# wacky-hat.net
KiCad netlist of a schematic drawn in Altium Designer
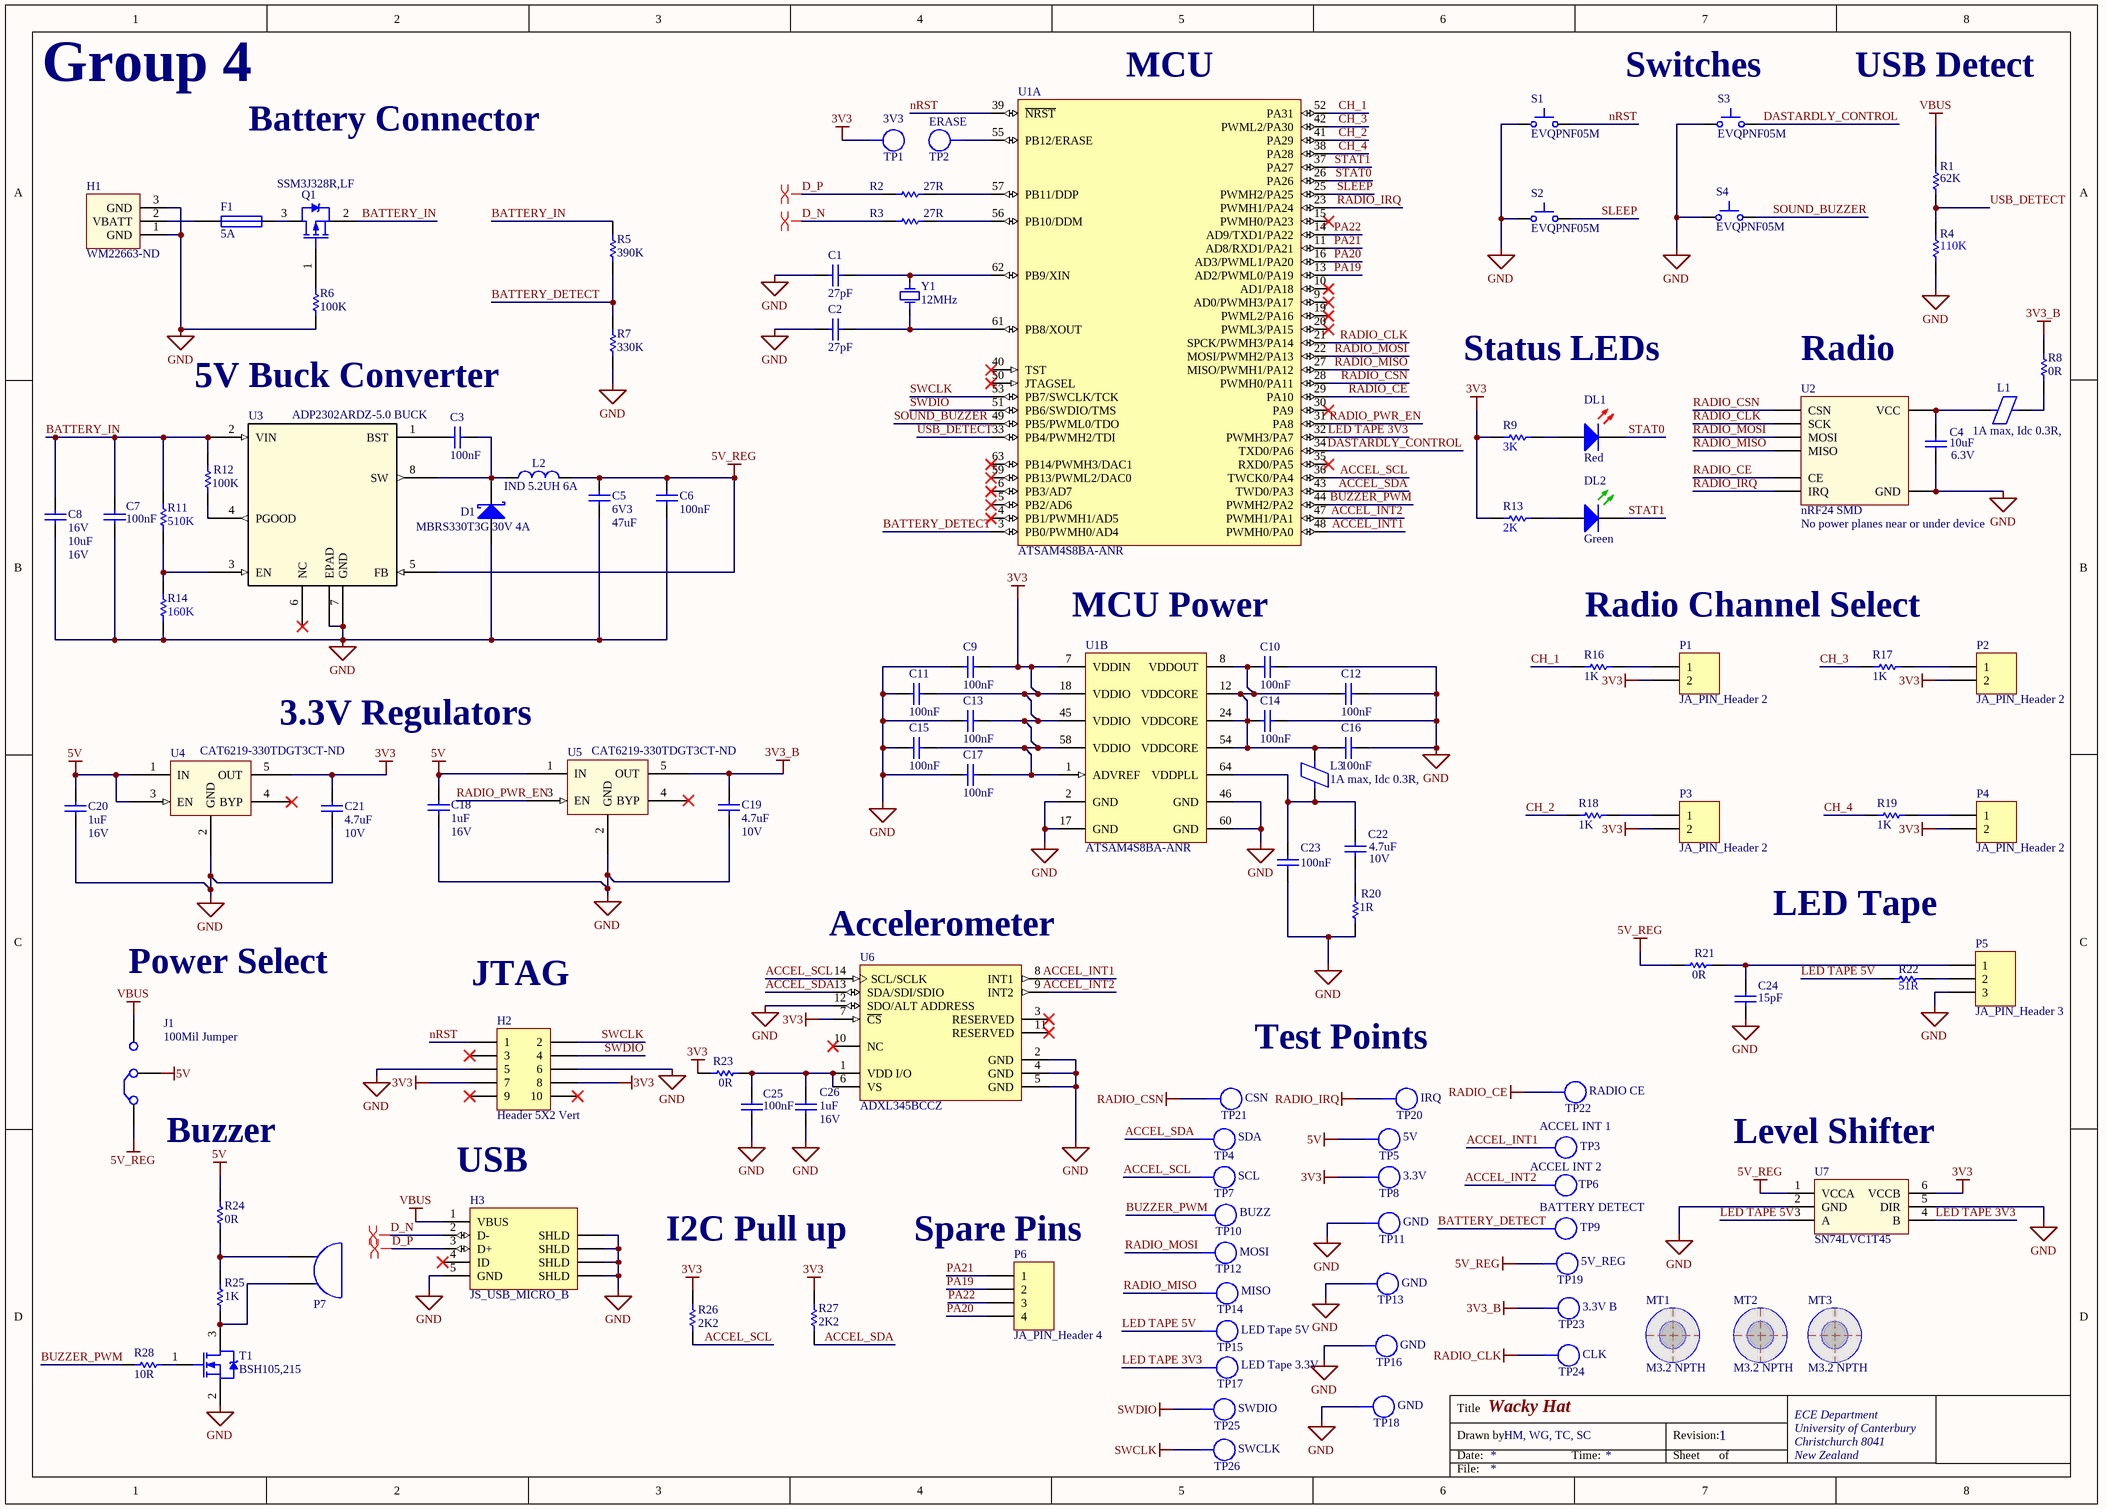
[diagram p0: wacky-hat.SchDoc]

(export (version "E")
  (design (tool "Eeschema 10.0.6"))
  (components
    (comp (ref "C1")
      (value "27pF")
      (footprint "CAPC1608L")
      (description "CAP CER 27pF NPO/COG +-5% 50V 0603")
      (libsource (lib "ECE AD19Components_22V1") (part "CC_27pF_0603"))
    )
    (comp (ref "C2")
      (value "27pF")
      (footprint "CAPC1608L")
      (description "CAP CER 27pF NPO/COG +-5% 50V 0603")
      (libsource (lib "ECE AD19Components_22V1") (part "CC_27pF_0603"))
    )
    (comp (ref "C3")
      (value "100nF")
      (footprint "CAPC1608L")
      (description "CAP CER 100nF X7R +-10% 50V 0603")
      (libsource (lib "ECE AD19Components_22V1") (part "CC_100nF_0603"))
    )
    (comp (ref "C4")
      (value "10uF")
      (footprint "CAPC1608L")
      (description "CAP CER 10UF X5R +-20% 6V3 0603")
      (fields (field (name "VOLTAGE - RATED") "6.3V"))
      (libsource (lib "ECE AD19Components_22V1") (part "CC_10uF_0603"))
    )
    (comp (ref "C5")
      (value "CC_47uF_0805_6V3")
      (footprint "CAPC2012N")
      (description "SAMSUNG ELECTRO-MECHANICS - CL21A476MQCLRNC - CAP, 47UF, 6.3V, MLCC, 0805")
      (fields
        (field (name "TOLERANCE") "20%")
        (field (name "VOLTAGE RATING") "6V3")
        (field (name "CAPACITANCE") "47uF")
      )
      (libsource (lib "ECE AD19Components_22V1") (part "CC_47uF_0805_6V3"))
    )
    (comp (ref "C6")
      (value "100nF")
      (footprint "CAPC1608L")
      (description "CAP CER 100nF X7R +-10% 50V 0603")
      (libsource (lib "ECE AD19Components_22V1") (part "CC_100nF_0603"))
    )
    (comp (ref "C7")
      (value "100nF")
      (footprint "CAPC1608L")
      (description "CAP CER 100nF X7R +-10% 50V 0603")
      (libsource (lib "ECE AD19Components_22V1") (part "CC_100nF_0603"))
    )
    (comp (ref "C8")
      (value "10uF")
      (footprint "CAPC2012L")
      (description "CAP CER 10uF X5R 16V 0805")
      (fields
        (field (name "MANUFACTURER") "Samsung Electro-Mechanics")
        (field (name "MANUFACTURER PART NUMBER") "CL21A106KOQNNWE")
        (field (name "VOLTAGE - RATED") "16V")
        (field (name "MAX VOLTAGE") "16V")
      )
      (libsource (lib "ECE AD19Components_22V1") (part "CC_10uF_0805_16V"))
    )
    (comp (ref "C9")
      (value "100nF")
      (footprint "CAPC1608L")
      (description "CAP CER 100nF X7R +-10% 50V 0603")
      (libsource (lib "ECE AD19Components_22V1") (part "CC_100nF_0603"))
    )
    (comp (ref "C10")
      (value "100nF")
      (footprint "CAPC1608L")
      (description "CAP CER 100nF X7R +-10% 50V 0603")
      (libsource (lib "ECE AD19Components_22V1") (part "CC_100nF_0603"))
    )
    (comp (ref "C11")
      (value "100nF")
      (footprint "CAPC1608L")
      (description "CAP CER 100nF X7R +-10% 50V 0603")
      (libsource (lib "ECE AD19Components_22V1") (part "CC_100nF_0603"))
    )
    (comp (ref "C12")
      (value "100nF")
      (footprint "CAPC1608L")
      (description "CAP CER 100nF X7R +-10% 50V 0603")
      (libsource (lib "ECE AD19Components_22V1") (part "CC_100nF_0603"))
    )
    (comp (ref "C13")
      (value "100nF")
      (footprint "CAPC1608L")
      (description "CAP CER 100nF X7R +-10% 50V 0603")
      (libsource (lib "ECE AD19Components_22V1") (part "CC_100nF_0603"))
    )
    (comp (ref "C14")
      (value "100nF")
      (footprint "CAPC1608L")
      (description "CAP CER 100nF X7R +-10% 50V 0603")
      (libsource (lib "ECE AD19Components_22V1") (part "CC_100nF_0603"))
    )
    (comp (ref "C15")
      (value "100nF")
      (footprint "CAPC1608L")
      (description "CAP CER 100nF X7R +-10% 50V 0603")
      (libsource (lib "ECE AD19Components_22V1") (part "CC_100nF_0603"))
    )
    (comp (ref "C16")
      (value "100nF")
      (footprint "CAPC1608L")
      (description "CAP CER 100nF X7R +-10% 50V 0603")
      (libsource (lib "ECE AD19Components_22V1") (part "CC_100nF_0603"))
    )
    (comp (ref "C17")
      (value "100nF")
      (footprint "CAPC1608L")
      (description "CAP CER 100nF X7R +-10% 50V 0603")
      (libsource (lib "ECE AD19Components_22V1") (part "CC_100nF_0603"))
    )
    (comp (ref "C18")
      (value "1uF")
      (footprint "CAPC1608L")
      (description "CAP CER 1uF Y5V -20% +80% 16V 0603")
      (fields (field (name "MAX VOLTAGE") "16V"))
      (libsource (lib "ECE AD19Components_22V1") (part "CC_1uF_0603"))
    )
    (comp (ref "C19")
      (value "4.7uF")
      (footprint "CAPC1608N")
      (description "CAP CER 4.7uF X5R +-20%  10V 0603")
      (fields (field (name "MAX VOLTAGE") "10V"))
      (libsource (lib "ECE AD19Components_22V1") (part "CC_4.7uF_0603"))
    )
    (comp (ref "C20")
      (value "1uF")
      (footprint "CAPC1608L")
      (description "CAP CER 1uF Y5V -20% +80% 16V 0603")
      (fields (field (name "MAX VOLTAGE") "16V"))
      (libsource (lib "ECE AD19Components_22V1") (part "CC_1uF_0603"))
    )
    (comp (ref "C21")
      (value "4.7uF")
      (footprint "CAPC1608N")
      (description "CAP CER 4.7uF X5R +-20%  10V 0603")
      (fields (field (name "MAX VOLTAGE") "10V"))
      (libsource (lib "ECE AD19Components_22V1") (part "CC_4.7uF_0603"))
    )
    (comp (ref "C22")
      (value "4.7uF")
      (footprint "CAPC1608N")
      (description "CAP CER 4.7uF X5R +-20%  10V 0603")
      (fields (field (name "MAX VOLTAGE") "10V"))
      (libsource (lib "ECE AD19Components_22V1") (part "CC_4.7uF_0603"))
    )
    (comp (ref "C23")
      (value "100nF")
      (footprint "CAPC1608L")
      (description "CAP CER 100nF X7R +-10% 50V 0603")
      (libsource (lib "ECE AD19Components_22V1") (part "CC_100nF_0603"))
    )
    (comp (ref "C24")
      (value "15pF")
      (footprint "CAPC1608L")
      (description "CAP CER 15pF NPO/COG +-5% 50V 0603")
      (libsource (lib "ECE AD19Components_22V1") (part "CC_15pF_0603"))
    )
    (comp (ref "C25")
      (value "100nF")
      (footprint "CAPC1608L")
      (description "CAP CER 100nF X7R +-10% 50V 0603")
      (libsource (lib "ECE AD19Components_22V1") (part "CC_100nF_0603"))
    )
    (comp (ref "C26")
      (value "1uF")
      (footprint "CAPC1608L")
      (description "CAP CER 1uF Y5V -20% +80% 16V 0603")
      (fields (field (name "MAX VOLTAGE") "16V"))
      (libsource (lib "ECE AD19Components_22V1") (part "CC_1uF_0603"))
    )
    (comp (ref "D1")
      (value "MBRS330T3G 30V 4A")
      (footprint "SMC")
      (description "SCHOTTKY  30V 4A")
      (fields
        (field (name "MANUFACTURER") "ON Semiconductor")
        (field (name "MANUFACTURER PART NUMBER") "MBRS330T3G")
      )
      (libsource (lib "ENCE461AD19_V23") (part "MBRS330T3G"))
    )
    (comp (ref "DL1")
      (value "Red")
      (footprint "WL-SMCW0603")
      (description "LED Red 250mcd 0603 SMD")
      (fields
        (field (name "MANUFACTURER") "WURTH ELEKTRONIK")
        (field (name "MANUFACTURER PART NUMBER") "150060RS75000")
        (field (name "LED COLOUR") "Red")
      )
      (libsource (lib "ECE AD19Components_22V1") (part "DL_150060RS75000"))
    )
    (comp (ref "DL2")
      (value "Green")
      (footprint "WL-SMCW0603")
      (description "LED Green 430mcd 0603 SMD")
      (fields
        (field (name "MANUFACTURER") "WURTH ELEKTRONIK")
        (field (name "MANUFACTURER PART NUMBER") "150060GS75000")
        (field (name "LED COLOUR") "Green")
      )
      (libsource (lib "ECE AD19Components_22V1") (part "DL_150060GS75000"))
    )
    (comp (ref "F1")
      (value "5A")
      (footprint "RESC3216N")
      (description "Fuse 5.0A Fast Acting 1206 SMD")
      (fields (field (name "MANUFACTURER PART NUMBER") "C1F5") (field (name "MANUFACTURER") "Bel TRP"))
      (libsource (lib "ECE AD19Components_22V1") (part "FS_Fuse_5.0A"))
    )
    (comp (ref "H1")
      (value "Battery_HEADER_3pin")
      (footprint "BATT_HEADER_3POS")
      (description "3Pin Header 2.54mm spacing\r\nDigikey #WM22663-ND")
      (fields (field (name "SUPPLIER PART NUMBER 1") "WM22663-ND"))
      (libsource (lib "ENCE461AD19_V23") (part "Battery_HEADER_3pin"))
    )
    (comp (ref "H2")
      (value "Header 5X2 Vert")
      (footprint "IDC2.54-V10D")
      (description "IDC Header, 2,54mm, 10-Pin, Vert")
      (libsource (lib "ECE AD19Components_22V1") (part "JA_HDR_IDC_5X2_VERT"))
    )
    (comp (ref "H3")
      (value "JS_USB_MICRO_B")
      (footprint "FCI_USB_10118194-0001LF")
      (description "CONN USB MICRO B RECPT SMT R/A")
      (fields (field (name "MANUFACTURER") "FCI") (field (name "MANUFACTURER PART NUMBER") "10118194-0001LF"))
      (libsource (lib "ECE AD19Components_22V1") (part "JS_USB_MICRO_B_SMT"))
    )
    (comp (ref "J1")
      (value "100Mil Jumper")
      (footprint "JMP2.54-CO")
      (description "2.54mm Jumper change over, Thru Hole")
      (libsource (lib "ECE AD19Components_22V1") (part "TP_JUMPER_CO"))
    )
    (comp (ref "L1")
      (value "1A max, Idc 0.3R,")
      (footprint "INDC3216L")
      (description "Ferrite Bead, Rdc 0.3R, Z100MHZ 600R, Imax 1A, SMD 1206")
      (fields
        (field (name "MANUFACTURER") "FAIR-RITE")
        (field (name "MANUFACTURER PART NUMBER") "2512066017Y1")
      )
      (libsource (lib "ECE AD19Components_22V1") (part "IN_Ferrite-Bead"))
    )
    (comp (ref "L2")
      (value "IND 5.2UH 6A")
      (footprint "INDUCTOR5u2")
      (description "FIXED IND 5.2UH 6A 22 MOHM SMD")
      (fields
        (field (name "MANUFACTURER") "Sumida America Components Inc.")
        (field (name "MANUFACTURER PART NUMBER") "CDRH104RNP-5R2NC")
      )
      (libsource (lib "ENCE461AD19_V23") (part "CDRH104RNP-5R2NC"))
    )
    (comp (ref "L3")
      (value "1A max, Idc 0.3R,")
      (footprint "INDC3216L")
      (description "Ferrite Bead, Rdc 0.3R, Z100MHZ 600R, Imax 1A, SMD 1206")
      (fields
        (field (name "MANUFACTURER") "FAIR-RITE")
        (field (name "MANUFACTURER PART NUMBER") "2512066017Y1")
      )
      (libsource (lib "ECE AD19Components_22V1") (part "IN_Ferrite-Bead"))
    )
    (comp (ref "MT1")
      (value "M3.2 NPTH")
      (footprint "MNT-HOLE_3.2mm_NPTH")
      (description "Fixing M3.2 Mount Hole NPTH")
      (fields (field (name "MANUFACTURER") "Hi-Q"))
      (libsource (lib "ECE AD19Components_22V1") (part "MC_M3.2_HOLE"))
    )
    (comp (ref "MT2")
      (value "M3.2 NPTH")
      (footprint "MNT-HOLE_3.2mm_NPTH")
      (description "Fixing M3.2 Mount Hole NPTH")
      (fields (field (name "MANUFACTURER") "Hi-Q"))
      (libsource (lib "ECE AD19Components_22V1") (part "MC_M3.2_HOLE"))
    )
    (comp (ref "MT3")
      (value "M3.2 NPTH")
      (footprint "MNT-HOLE_3.2mm_NPTH")
      (description "Fixing M3.2 Mount Hole NPTH")
      (fields (field (name "MANUFACTURER") "Hi-Q"))
      (libsource (lib "ECE AD19Components_22V1") (part "MC_M3.2_HOLE"))
    )
    (comp (ref "P1")
      (value "JA_PIN_Header 2")
      (footprint "HDR1X2")
      (description "Header, 2-Pin")
      (fields (field (name "PUBLISHER") "Altium Limited"))
      (libsource (lib "ECE AD19Components_22V1") (part "JA_PIN_Header 2"))
    )
    (comp (ref "P2")
      (value "JA_PIN_Header 2")
      (footprint "HDR1X2")
      (description "Header, 2-Pin")
      (fields (field (name "PUBLISHER") "Altium Limited"))
      (libsource (lib "ECE AD19Components_22V1") (part "JA_PIN_Header 2"))
    )
    (comp (ref "P3")
      (value "JA_PIN_Header 2")
      (footprint "HDR1X2")
      (description "Header, 2-Pin")
      (fields (field (name "PUBLISHER") "Altium Limited"))
      (libsource (lib "ECE AD19Components_22V1") (part "JA_PIN_Header 2"))
    )
    (comp (ref "P4")
      (value "JA_PIN_Header 2")
      (footprint "HDR1X2")
      (description "Header, 2-Pin")
      (fields (field (name "PUBLISHER") "Altium Limited"))
      (libsource (lib "ECE AD19Components_22V1") (part "JA_PIN_Header 2"))
    )
    (comp (ref "P5")
      (value "JA_PIN_Header 3")
      (footprint "HDR1X3")
      (description "Header, 3-Pin")
      (fields (field (name "PUBLISHER") "Altium Limited"))
      (libsource (lib "ECE AD19Components_22V1") (part "JA_PIN_Header 3"))
    )
    (comp (ref "P6")
      (value "JA_PIN_Header 4")
      (footprint "HDR1X4")
      (description "Header, 4-Pin")
      (fields (field (name "PUBLISHER") "Altium Limited"))
      (libsource (lib "ECE AD19Components_22V1") (part "JA_PIN_Header 4"))
    )
    (comp (ref "P7")
      (value "Piezo Buzzer")
      (footprint "BUZZER")
      (description "TDK - PS1240P02BT - BUZZER, PIEZO, 70DB, 12.2MM")
      (libsource (lib "ENCE461AD19_V23") (part "Piezo Buzzer"))
    )
    (comp (ref "Q1")
      (value "SSM3J328R,LF")
      (footprint "SOT23_L")
      (description "MOSFET P-CH 20V 6A SOT23-3")
      (fields
        (field (name "MANUFACTURER") "Toshiba")
        (field (name "MANUFACTURER PART NUMBER") "SSM3J328R,LF")
      )
      (libsource (lib "ECE AD19Components_22V1") (part "TM_SSM3J328R"))
    )
    (comp (ref "R1")
      (value "62K")
      (footprint "RESC1608L")
      (description "RES 62.0K OHM 1/10W 5% 0603 SMD")
      (libsource (lib "ECE AD19Components_22V1") (part "RS_62K"))
    )
    (comp (ref "R2")
      (value "27R")
      (footprint "RESC1608L")
      (description "RES 27 OHM 1/10W 5% 0603 SMD")
      (libsource (lib "ECE AD19Components_22V1") (part "RS_27R"))
    )
    (comp (ref "R3")
      (value "27R")
      (footprint "RESC1608L")
      (description "RES 27 OHM 1/10W 5% 0603 SMD")
      (libsource (lib "ECE AD19Components_22V1") (part "RS_27R"))
    )
    (comp (ref "R4")
      (value "110K")
      (footprint "RESC1608L")
      (description "RES 110K OHM 1/10W 5% 0603 SMD")
      (libsource (lib "ECE AD19Components_22V1") (part "RS_110K"))
    )
    (comp (ref "R5")
      (value "390K")
      (footprint "RESC1608L")
      (description "RES 390K OHM 1/10W 5% 0603 SMD")
      (libsource (lib "ECE AD19Components_22V1") (part "RS_390K"))
    )
    (comp (ref "R6")
      (value "100K")
      (footprint "RESC1608L")
      (description "RES 100K OHM 1/10W 5% 0603 SMD")
      (libsource (lib "ECE AD19Components_22V1") (part "RS_100K"))
    )
    (comp (ref "R7")
      (value "330K")
      (footprint "RESC1608L")
      (description "RES 330K OHM 1/10W 5% 0603 SMD")
      (libsource (lib "ECE AD19Components_22V1") (part "RS_330K"))
    )
    (comp (ref "R8")
      (value "0R")
      (footprint "RESC1608L")
      (description "RES 0.0 OHM 1/10W 5% 0603 SMD")
      (libsource (lib "ECE AD19Components_22V1") (part "RS_0R0"))
    )
    (comp (ref "R9")
      (value "3K")
      (footprint "RESC1608L")
      (description "RES 3K OHM 1/10W 5% 0603 SMD")
      (libsource (lib "ECE AD19Components_22V1") (part "RS_3K"))
    )
    (comp (ref "R11")
      (value "510K")
      (footprint "RESC1608L")
      (description "RES 510K OHM 1/10W 5% 0603 SMD")
      (libsource (lib "ECE AD19Components_22V1") (part "RS_510K"))
    )
    (comp (ref "R12")
      (value "100K")
      (footprint "RESC1608L")
      (description "RES 100K OHM 1/10W 5% 0603 SMD")
      (libsource (lib "ECE AD19Components_22V1") (part "RS_100K"))
    )
    (comp (ref "R13")
      (value "2K")
      (footprint "RESC1608L")
      (description "RES 2K OHM 1/10W 5% 0603 SMD")
      (libsource (lib "ECE AD19Components_22V1") (part "RS_2K"))
    )
    (comp (ref "R14")
      (value "160K")
      (footprint "RESC1608L")
      (description "RES 160K OHM 1/10W 5% 0603 SMD")
      (libsource (lib "ECE AD19Components_22V1") (part "RS_160K"))
    )
    (comp (ref "R16")
      (value "1K")
      (footprint "RESC1608L")
      (description "RES 1.0K OHM 1/10W 5% 0603 SMD")
      (libsource (lib "ECE AD19Components_22V1") (part "RS_1K"))
    )
    (comp (ref "R17")
      (value "1K")
      (footprint "RESC1608L")
      (description "RES 1.0K OHM 1/10W 5% 0603 SMD")
      (libsource (lib "ECE AD19Components_22V1") (part "RS_1K"))
    )
    (comp (ref "R18")
      (value "1K")
      (footprint "RESC1608L")
      (description "RES 1.0K OHM 1/10W 5% 0603 SMD")
      (libsource (lib "ECE AD19Components_22V1") (part "RS_1K"))
    )
    (comp (ref "R19")
      (value "1K")
      (footprint "RESC1608L")
      (description "RES 1.0K OHM 1/10W 5% 0603 SMD")
      (libsource (lib "ECE AD19Components_22V1") (part "RS_1K"))
    )
    (comp (ref "R20")
      (value "1R")
      (footprint "RESC3216L")
      (description "RES 1R OHM 1/4W 5% 1206 SMD")
      (libsource (lib "ECE AD19Components_22V1") (part "RT_1R"))
    )
    (comp (ref "R21")
      (value "0R")
      (footprint "RESC1608L")
      (description "RES 0.0 OHM 1/10W 5% 0603 SMD")
      (libsource (lib "ECE AD19Components_22V1") (part "RS_0R0"))
    )
    (comp (ref "R22")
      (value "51R")
      (footprint "RESC1608L")
      (description "RES 51 OHM 1/10W 5% 0603 SMD")
      (libsource (lib "ECE AD19Components_22V1") (part "RS_51R"))
    )
    (comp (ref "R23")
      (value "0R")
      (footprint "RESC1608L")
      (description "RES 0.0 OHM 1/10W 5% 0603 SMD")
      (libsource (lib "ECE AD19Components_22V1") (part "RS_0R0"))
    )
    (comp (ref "R24")
      (value "0R")
      (footprint "RESC1608L")
      (description "RES 0.0 OHM 1/10W 5% 0603 SMD")
      (libsource (lib "ECE AD19Components_22V1") (part "RS_0R0"))
    )
    (comp (ref "R25")
      (value "1K")
      (footprint "RESC1608L")
      (description "RES 1.0K OHM 1/10W 5% 0603 SMD")
      (libsource (lib "ECE AD19Components_22V1") (part "RS_1K"))
    )
    (comp (ref "R26")
      (value "2K2")
      (footprint "RESC1608L")
      (description "RES 2.2K OHM 1/10W 5% 0603 SMD")
      (libsource (lib "ECE AD19Components_22V1") (part "RS_2K2"))
    )
    (comp (ref "R27")
      (value "2K2")
      (footprint "RESC1608L")
      (description "RES 2.2K OHM 1/10W 5% 0603 SMD")
      (libsource (lib "ECE AD19Components_22V1") (part "RS_2K2"))
    )
    (comp (ref "R28")
      (value "10R")
      (footprint "RESC1608L")
      (description "RES 10 OHM 1/10W 5% 0603 SMD")
      (libsource (lib "ECE AD19Components_22V1") (part "RS_10R"))
    )
    (comp (ref "S1")
      (value "EVQPNF05M")
      (footprint "EVQPNF05M")
      (description "Panasonic 6 x 3.5mm SMD Light Touch Switch Type SMD")
      (fields (field (name "MANUFACTURER") "Panasonic"))
      (libsource (lib "ECE AD19Components_22V1") (part "WS_EVQPNF05M"))
    )
    (comp (ref "S2")
      (value "EVQPNF05M")
      (footprint "EVQPNF05M")
      (description "Panasonic 6 x 3.5mm SMD Light Touch Switch Type SMD")
      (fields (field (name "MANUFACTURER") "Panasonic"))
      (libsource (lib "ECE AD19Components_22V1") (part "WS_EVQPNF05M"))
    )
    (comp (ref "S3")
      (value "EVQPNF05M")
      (footprint "EVQPNF05M")
      (description "Panasonic 6 x 3.5mm SMD Light Touch Switch Type SMD")
      (fields (field (name "MANUFACTURER") "Panasonic"))
      (libsource (lib "ECE AD19Components_22V1") (part "WS_EVQPNF05M"))
    )
    (comp (ref "S4")
      (value "EVQPNF05M")
      (footprint "EVQPNF05M")
      (description "Panasonic 6 x 3.5mm SMD Light Touch Switch Type SMD")
      (fields (field (name "MANUFACTURER") "Panasonic"))
      (libsource (lib "ECE AD19Components_22V1") (part "WS_EVQPNF05M"))
    )
    (comp (ref "T1")
      (value "BSH105,215")
      (footprint "SOT23_L")
      (description "MOSFET N-CH 20V 1.05A SOT-23")
      (fields
        (field (name "MANUFACTURER") "NXP Semiconductors")
        (field (name "MANUFACTURER PART NUMBER") "BSH105,215")
      )
      (libsource (lib "ECE AD19Components_22V1") (part "TM_BSH105"))
    )
    (comp (ref "TP1")
      (value "3V3")
      (footprint "TP_1206")
      (description "Test-Point 3.3x1.6x2.1mm SMD")
      (fields
        (field (name "MANUFACTURER") "Harwin Inc")
        (field (name "MANUFACTURER PART NUMBER") "S1751-46R")
      )
      (libsource (lib "ECE AD19Components_22V1") (part "TP_1206"))
    )
    (comp (ref "TP2")
      (value "ERASE")
      (footprint "TP_1206")
      (description "Test-Point 3.3x1.6x2.1mm SMD")
      (fields
        (field (name "MANUFACTURER") "Harwin Inc")
        (field (name "MANUFACTURER PART NUMBER") "S1751-46R")
      )
      (libsource (lib "ECE AD19Components_22V1") (part "TP_1206"))
    )
    (comp (ref "TP3")
      (value "ACCEL INT 1")
      (footprint "TP_1206")
      (description "Test-Point 3.3x1.6x2.1mm SMD")
      (fields
        (field (name "MANUFACTURER") "Harwin Inc")
        (field (name "MANUFACTURER PART NUMBER") "S1751-46R")
      )
      (libsource (lib "ECE AD19Components_22V1") (part "TP_1206"))
    )
    (comp (ref "TP4")
      (value "SDA")
      (footprint "TP_1206")
      (description "Test-Point 3.3x1.6x2.1mm SMD")
      (fields
        (field (name "MANUFACTURER") "Harwin Inc")
        (field (name "MANUFACTURER PART NUMBER") "S1751-46R")
      )
      (libsource (lib "ECE AD19Components_22V1") (part "TP_1206"))
    )
    (comp (ref "TP5")
      (value "5V")
      (footprint "TP_1206")
      (description "Test-Point 3.3x1.6x2.1mm SMD")
      (fields
        (field (name "MANUFACTURER") "Harwin Inc")
        (field (name "MANUFACTURER PART NUMBER") "S1751-46R")
      )
      (libsource (lib "ECE AD19Components_22V1") (part "TP_1206"))
    )
    (comp (ref "TP6")
      (value "ACCEL INT 2")
      (footprint "TP_1206")
      (description "Test-Point 3.3x1.6x2.1mm SMD")
      (fields
        (field (name "MANUFACTURER") "Harwin Inc")
        (field (name "MANUFACTURER PART NUMBER") "S1751-46R")
      )
      (libsource (lib "ECE AD19Components_22V1") (part "TP_1206"))
    )
    (comp (ref "TP7")
      (value "SCL")
      (footprint "TP_1206")
      (description "Test-Point 3.3x1.6x2.1mm SMD")
      (fields
        (field (name "MANUFACTURER") "Harwin Inc")
        (field (name "MANUFACTURER PART NUMBER") "S1751-46R")
      )
      (libsource (lib "ECE AD19Components_22V1") (part "TP_1206"))
    )
    (comp (ref "TP8")
      (value "3.3V")
      (footprint "TP_1206")
      (description "Test-Point 3.3x1.6x2.1mm SMD")
      (fields
        (field (name "MANUFACTURER") "Harwin Inc")
        (field (name "MANUFACTURER PART NUMBER") "S1751-46R")
      )
      (libsource (lib "ECE AD19Components_22V1") (part "TP_1206"))
    )
    (comp (ref "TP9")
      (value "BATTERY DETECT")
      (footprint "TP_1206")
      (description "Test-Point 3.3x1.6x2.1mm SMD")
      (fields
        (field (name "MANUFACTURER") "Harwin Inc")
        (field (name "MANUFACTURER PART NUMBER") "S1751-46R")
      )
      (libsource (lib "ECE AD19Components_22V1") (part "TP_1206"))
    )
    (comp (ref "TP10")
      (value "BUZZ")
      (footprint "TP_1206")
      (description "Test-Point 3.3x1.6x2.1mm SMD")
      (fields
        (field (name "MANUFACTURER") "Harwin Inc")
        (field (name "MANUFACTURER PART NUMBER") "S1751-46R")
      )
      (libsource (lib "ECE AD19Components_22V1") (part "TP_1206"))
    )
    (comp (ref "TP11")
      (value "GND")
      (footprint "TP_1206")
      (description "Test-Point 3.3x1.6x2.1mm SMD")
      (fields
        (field (name "MANUFACTURER") "Harwin Inc")
        (field (name "MANUFACTURER PART NUMBER") "S1751-46R")
      )
      (libsource (lib "ECE AD19Components_22V1") (part "TP_1206"))
    )
    (comp (ref "TP12")
      (value "MOSI")
      (footprint "TP_1206")
      (description "Test-Point 3.3x1.6x2.1mm SMD")
      (fields
        (field (name "MANUFACTURER") "Harwin Inc")
        (field (name "MANUFACTURER PART NUMBER") "S1751-46R")
      )
      (libsource (lib "ECE AD19Components_22V1") (part "TP_1206"))
    )
    (comp (ref "TP13")
      (value "GND")
      (footprint "TP_1206")
      (description "Test-Point 3.3x1.6x2.1mm SMD")
      (fields
        (field (name "MANUFACTURER") "Harwin Inc")
        (field (name "MANUFACTURER PART NUMBER") "S1751-46R")
      )
      (libsource (lib "ECE AD19Components_22V1") (part "TP_1206"))
    )
    (comp (ref "TP14")
      (value "MISO")
      (footprint "TP_1206")
      (description "Test-Point 3.3x1.6x2.1mm SMD")
      (fields
        (field (name "MANUFACTURER") "Harwin Inc")
        (field (name "MANUFACTURER PART NUMBER") "S1751-46R")
      )
      (libsource (lib "ECE AD19Components_22V1") (part "TP_1206"))
    )
    (comp (ref "TP15")
      (value "LED Tape 5V")
      (footprint "TP_1206")
      (description "Test-Point 3.3x1.6x2.1mm SMD")
      (fields
        (field (name "MANUFACTURER") "Harwin Inc")
        (field (name "MANUFACTURER PART NUMBER") "S1751-46R")
      )
      (libsource (lib "ECE AD19Components_22V1") (part "TP_1206"))
    )
    (comp (ref "TP16")
      (value "GND")
      (footprint "TP_1206")
      (description "Test-Point 3.3x1.6x2.1mm SMD")
      (fields
        (field (name "MANUFACTURER") "Harwin Inc")
        (field (name "MANUFACTURER PART NUMBER") "S1751-46R")
      )
      (libsource (lib "ECE AD19Components_22V1") (part "TP_1206"))
    )
    (comp (ref "TP17")
      (value "LED Tape 3.3V")
      (footprint "TP_1206")
      (description "Test-Point 3.3x1.6x2.1mm SMD")
      (fields
        (field (name "MANUFACTURER") "Harwin Inc")
        (field (name "MANUFACTURER PART NUMBER") "S1751-46R")
      )
      (libsource (lib "ECE AD19Components_22V1") (part "TP_1206"))
    )
    (comp (ref "TP18")
      (value "GND")
      (footprint "TP_1206")
      (description "Test-Point 3.3x1.6x2.1mm SMD")
      (fields
        (field (name "MANUFACTURER") "Harwin Inc")
        (field (name "MANUFACTURER PART NUMBER") "S1751-46R")
      )
      (libsource (lib "ECE AD19Components_22V1") (part "TP_1206"))
    )
    (comp (ref "TP19")
      (value "5V_REG")
      (footprint "TP_1206")
      (description "Test-Point 3.3x1.6x2.1mm SMD")
      (fields
        (field (name "MANUFACTURER") "Harwin Inc")
        (field (name "MANUFACTURER PART NUMBER") "S1751-46R")
      )
      (libsource (lib "ECE AD19Components_22V1") (part "TP_1206"))
    )
    (comp (ref "TP20")
      (value "IRQ")
      (footprint "TP_1206")
      (description "Test-Point 3.3x1.6x2.1mm SMD")
      (fields
        (field (name "MANUFACTURER") "Harwin Inc")
        (field (name "MANUFACTURER PART NUMBER") "S1751-46R")
      )
      (libsource (lib "ECE AD19Components_22V1") (part "TP_1206"))
    )
    (comp (ref "TP21")
      (value "CSN")
      (footprint "TP_1206")
      (description "Test-Point 3.3x1.6x2.1mm SMD")
      (fields
        (field (name "MANUFACTURER") "Harwin Inc")
        (field (name "MANUFACTURER PART NUMBER") "S1751-46R")
      )
      (libsource (lib "ECE AD19Components_22V1") (part "TP_1206"))
    )
    (comp (ref "TP22")
      (value "RADIO CE")
      (footprint "TP_1206")
      (description "Test-Point 3.3x1.6x2.1mm SMD")
      (fields
        (field (name "MANUFACTURER") "Harwin Inc")
        (field (name "MANUFACTURER PART NUMBER") "S1751-46R")
      )
      (libsource (lib "ECE AD19Components_22V1") (part "TP_1206"))
    )
    (comp (ref "TP23")
      (value "3.3V B")
      (footprint "TP_1206")
      (description "Test-Point 3.3x1.6x2.1mm SMD")
      (fields
        (field (name "MANUFACTURER") "Harwin Inc")
        (field (name "MANUFACTURER PART NUMBER") "S1751-46R")
      )
      (libsource (lib "ECE AD19Components_22V1") (part "TP_1206"))
    )
    (comp (ref "TP24")
      (value "CLK")
      (footprint "TP_1206")
      (description "Test-Point 3.3x1.6x2.1mm SMD")
      (fields
        (field (name "MANUFACTURER") "Harwin Inc")
        (field (name "MANUFACTURER PART NUMBER") "S1751-46R")
      )
      (libsource (lib "ECE AD19Components_22V1") (part "TP_1206"))
    )
    (comp (ref "TP25")
      (value "SWDIO")
      (footprint "TP_1206")
      (description "Test-Point 3.3x1.6x2.1mm SMD")
      (fields
        (field (name "MANUFACTURER") "Harwin Inc")
        (field (name "MANUFACTURER PART NUMBER") "S1751-46R")
      )
      (libsource (lib "ECE AD19Components_22V1") (part "TP_1206"))
    )
    (comp (ref "TP26")
      (value "SWCLK")
      (footprint "TP_1206")
      (description "Test-Point 3.3x1.6x2.1mm SMD")
      (fields
        (field (name "MANUFACTURER") "Harwin Inc")
        (field (name "MANUFACTURER PART NUMBER") "S1751-46R")
      )
      (libsource (lib "ECE AD19Components_22V1") (part "TP_1206"))
    )
    (comp (ref "U1")
      (value "ATSAM4S8BA-ANR")
      (footprint "LQFP64_L")
      (description "IC MCU 32BIT 512KB FLASH 64LQFP")
      (fields (field (name "MANUFACTURER") "Atmel"))
      (libsource (lib "ECE AD19Components_22V1") (part "SE_ATSAM4S16BA-MU"))
    )
    (comp (ref "U2")
      (value "nRF24 SMD")
      (footprint "NRF24")
      (description "nRF24 SMD Module")
      (fields (field (name "WARNING") "No power planes near or under device"))
      (libsource (lib "ENCE461AD19_V23") (part "NRF24"))
    )
    (comp (ref "U3")
      (value "ADP2302ARDZ-5.0 BUCK")
      (footprint "RD_8_1")
      (description "IC REG BUCK 5V 2A 8SOIC")
      (fields (field (name "MANUFACTURER_PART_NUMBER") "ADP2302ARDZ-5.0-R7"))
      (libsource (lib "ENCE461AD19_V23") (part "ADP2302ARDZ-5.0-R7"))
    )
    (comp (ref "U4")
      (value "CAT6219-330TDGT3")
      (footprint "SOT95P280X145-5N")
      (description "IC REG LIN 3.3V 500MA TSOT23-5")
      (fields
        (field (name "BASE PART NUMBER") "CAT6219")
        (field (name "SUPPLIER PART NUMBER") "CAT6219-330TDGT3CT-ND")
      )
      (libsource (lib "ENCE461AD19_V23") (part "SV_CAT6219-330TDGT3"))
    )
    (comp (ref "U5")
      (value "CAT6219-330TDGT3")
      (footprint "SOT95P280X145-5N")
      (description "IC REG LIN 3.3V 500MA TSOT23-5")
      (fields
        (field (name "BASE PART NUMBER") "CAT6219")
        (field (name "SUPPLIER PART NUMBER") "CAT6219-330TDGT3CT-ND")
      )
      (libsource (lib "ENCE461AD19_V23") (part "SV_CAT6219-330TDGT3"))
    )
    (comp (ref "U6")
      (value "ADXL345BCCZ")
      (footprint "ADI-CC-14-1_V")
      (fields (field (name "MANUFACTURER") "Analog Devices"))
      (libsource (lib "ENCE461AD19_V23") (part "ADXL345BCCZ"))
    )
    (comp (ref "U7")
      (value "SN74LVC1T45")
      (footprint "SOT23-6_N")
      (description "1.8V - 5V level converter")
      (libsource (lib "ENCE461AD19_V23") (part "SN74LVC1T45"))
    )
    (comp (ref "Y1")
      (value "12MHz")
      (footprint "6.0X3.5-4")
      (description "CRYSTAL 12MHZ 18PF 6X3.5mm SMD")
      (fields
        (field (name "MANUFACTURER") "CTS-Frequency Controls")
        (field (name "MANUFACTURER PART NUMBER") "406C35D12M00000")
        (field (name "FREQUENCY") "12MHz")
      )
      (libsource (lib "ECE AD19Components_22V1") (part "XT_CRYSTAL_12MHz_18pF"))
    )
  )
  (nets
    (net (code "2") (name "/ACCEL_INT1") (class "Default")
      (node (ref "TP3") (pin "1") (pinfunction "1_1") (pintype "passive"))
      (node (ref "U1") (pin "48") (pinfunction "PWMH0/PA0_48") (pintype "bidirectional"))
      (node (ref "U6") (pin "8") (pinfunction "INT1_8") (pintype "output"))
    )
    (net (code "3") (name "/ACCEL_INT2") (class "Default")
      (node (ref "TP6") (pin "1") (pinfunction "1_1") (pintype "passive"))
      (node (ref "U1") (pin "47") (pinfunction "PWMH1/PA1_47") (pintype "bidirectional"))
      (node (ref "U6") (pin "9") (pinfunction "INT2_9") (pintype "output"))
    )
    (net (code "4") (name "/ACCEL_SCL") (class "Default")
      (node (ref "R26") (pin "1") (pinfunction "1_1") (pintype "passive"))
      (node (ref "TP7") (pin "1") (pinfunction "1_1") (pintype "passive"))
      (node (ref "U1") (pin "36") (pinfunction "TWCK0/PA4_36") (pintype "bidirectional"))
      (node (ref "U6") (pin "14") (pinfunction "SCL/SCLK_14") (pintype "input"))
    )
    (net (code "5") (name "/ACCEL_SDA") (class "Default")
      (node (ref "R27") (pin "1") (pinfunction "1_1") (pintype "passive"))
      (node (ref "TP4") (pin "1") (pinfunction "1_1") (pintype "passive"))
      (node (ref "U1") (pin "43") (pinfunction "TWD0/PA3_43") (pintype "bidirectional"))
      (node (ref "U6") (pin "13") (pinfunction "SDA/SDI/SDIO_13") (pintype "bidirectional"))
    )
    (net (code "6") (name "/BATTERY_DETECT") (class "Default")
      (node (ref "R5") (pin "1") (pinfunction "1_1") (pintype "passive"))
      (node (ref "R7") (pin "2") (pinfunction "2_2") (pintype "passive"))
      (node (ref "TP9") (pin "1") (pinfunction "1_1") (pintype "passive"))
      (node (ref "U1") (pin "3") (pinfunction "PB0/PWMH0/AD4_3") (pintype "bidirectional"))
    )
    (net (code "7") (name "/BATTERY_IN") (class "Default")
      (node (ref "C7") (pin "2") (pinfunction "2_2") (pintype "passive"))
      (node (ref "C8") (pin "2") (pinfunction "2_2") (pintype "passive"))
      (node (ref "Q1") (pin "2") (pinfunction "2_2") (pintype "passive"))
      (node (ref "R11") (pin "2") (pinfunction "2_2") (pintype "passive"))
      (node (ref "R12") (pin "2") (pinfunction "2_2") (pintype "passive"))
      (node (ref "R5") (pin "2") (pinfunction "2_2") (pintype "passive"))
      (node (ref "U3") (pin "2") (pinfunction "VIN_2") (pintype "input"))
    )
    (net (code "8") (name "/BUZZER_PWM") (class "Default")
      (node (ref "R28") (pin "1") (pinfunction "1_1") (pintype "passive"))
      (node (ref "TP10") (pin "1") (pinfunction "1_1") (pintype "passive"))
      (node (ref "U1") (pin "44") (pinfunction "PWMH2/PA2_44") (pintype "bidirectional"))
    )
    (net (code "9") (name "/CH_1") (class "Default")
      (node (ref "R16") (pin "1") (pinfunction "1_1") (pintype "passive"))
      (node (ref "U1") (pin "52") (pinfunction "PA31_52") (pintype "bidirectional"))
    )
    (net (code "10") (name "/CH_2") (class "Default")
      (node (ref "R18") (pin "1") (pinfunction "1_1") (pintype "passive"))
      (node (ref "U1") (pin "41") (pinfunction "PA29_41") (pintype "bidirectional"))
    )
    (net (code "11") (name "/CH_3") (class "Default")
      (node (ref "R17") (pin "1") (pinfunction "1_1") (pintype "passive"))
      (node (ref "U1") (pin "42") (pinfunction "PWML2/PA30_42") (pintype "bidirectional"))
    )
    (net (code "12") (name "/CH_4") (class "Default")
      (node (ref "R19") (pin "1") (pinfunction "1_1") (pintype "passive"))
      (node (ref "U1") (pin "38") (pinfunction "PA28_38") (pintype "bidirectional"))
    )
    (net (code "13") (name "/DASTARDLY_CONTROL") (class "Default")
      (node (ref "S3") (pin "2") (pintype "passive"))
      (node (ref "U1") (pin "34") (pinfunction "TXD0/PA6_34") (pintype "bidirectional"))
    )
    (net (code "14") (name "/D_N") (class "Default")
      (node (ref "H3") (pin "2") (pinfunction "D-_2") (pintype "bidirectional"))
      (node (ref "R3") (pin "1") (pinfunction "1_1") (pintype "passive"))
    )
    (net (code "15") (name "/D_P") (class "Default")
      (node (ref "H3") (pin "3") (pinfunction "D+_3") (pintype "bidirectional"))
      (node (ref "R2") (pin "1") (pinfunction "1_1") (pintype "passive"))
    )
    (net (code "16") (name "/LED TAPE 3V3") (class "Default")
      (node (ref "TP17") (pin "1") (pinfunction "1_1") (pintype "passive"))
      (node (ref "U1") (pin "32") (pinfunction "PWMH3/PA7_32") (pintype "bidirectional"))
      (node (ref "U7") (pin "4") (pinfunction "B_4") (pintype "passive"))
    )
    (net (code "17") (name "/LED TAPE 5V") (class "Default")
      (node (ref "R22") (pin "1") (pinfunction "1_1") (pintype "passive"))
      (node (ref "TP15") (pin "1") (pinfunction "1_1") (pintype "passive"))
      (node (ref "U7") (pin "3") (pinfunction "A_3") (pintype "passive"))
    )
    (net (code "18") (name "/PA19") (class "Default")
      (node (ref "P6") (pin "2") (pinfunction "2_2") (pintype "passive"))
      (node (ref "U1") (pin "13") (pinfunction "AD2/PWML0/PA19_13") (pintype "bidirectional"))
    )
    (net (code "19") (name "/PA20") (class "Default")
      (node (ref "P6") (pin "4") (pinfunction "4_4") (pintype "passive"))
      (node (ref "U1") (pin "16") (pinfunction "AD3/PWML1/PA20_16") (pintype "bidirectional"))
    )
    (net (code "20") (name "/PA21") (class "Default")
      (node (ref "P6") (pin "1") (pinfunction "1_1") (pintype "passive"))
      (node (ref "U1") (pin "11") (pinfunction "AD8/RXD1/PA21_11") (pintype "bidirectional"))
    )
    (net (code "21") (name "/PA22") (class "Default")
      (node (ref "P6") (pin "3") (pinfunction "3_3") (pintype "passive"))
      (node (ref "U1") (pin "14") (pinfunction "AD9/TXD1/PA22_14") (pintype "bidirectional"))
    )
    (net (code "22") (name "/RADIO_MISO") (class "Default")
      (node (ref "TP14") (pin "1") (pinfunction "1_1") (pintype "passive"))
      (node (ref "U1") (pin "27") (pinfunction "MISO/PWMH1/PA12_27") (pintype "bidirectional"))
      (node (ref "U2") (pin "7") (pinfunction "MISO_7") (pintype "passive"))
    )
    (net (code "23") (name "/RADIO_MOSI") (class "Default")
      (node (ref "TP12") (pin "1") (pinfunction "1_1") (pintype "passive"))
      (node (ref "U1") (pin "22") (pinfunction "MOSI/PWMH2/PA13_22") (pintype "bidirectional"))
      (node (ref "U2") (pin "6") (pinfunction "MOSI_6") (pintype "passive"))
    )
    (net (code "24") (name "/RADIO_PWR_EN") (class "Default")
      (node (ref "U1") (pin "31") (pinfunction "PA8_31") (pintype "bidirectional"))
      (node (ref "U5") (pin "3") (pinfunction "EN_3") (pintype "input"))
    )
    (net (code "25") (name "/SLEEP") (class "Default")
      (node (ref "S2") (pin "2") (pintype "passive"))
      (node (ref "U1") (pin "25") (pinfunction "PWMH2/PA25_25") (pintype "bidirectional"))
    )
    (net (code "26") (name "/SOUND_BUZZER") (class "Default")
      (node (ref "S4") (pin "2") (pintype "passive"))
      (node (ref "U1") (pin "49") (pinfunction "PB5/PWML0/TDO_49") (pintype "bidirectional"))
    )
    (net (code "27") (name "/STAT0") (class "Default")
      (node (ref "DL1") (pin "1") (pinfunction "K_1") (pintype "passive"))
      (node (ref "U1") (pin "26") (pinfunction "PA26_26") (pintype "bidirectional"))
    )
    (net (code "28") (name "/STAT1") (class "Default")
      (node (ref "DL2") (pin "1") (pinfunction "K_1") (pintype "passive"))
      (node (ref "U1") (pin "37") (pinfunction "PA27_37") (pintype "bidirectional"))
    )
    (net (code "29") (name "/USB_DETECT") (class "Default")
      (node (ref "R1") (pin "1") (pinfunction "1_1") (pintype "passive"))
      (node (ref "R4") (pin "2") (pinfunction "2_2") (pintype "passive"))
      (node (ref "U1") (pin "33") (pinfunction "PB4/PWMH2/TDI_33") (pintype "bidirectional"))
    )
    (net (code "30") (name "/nRST") (class "Default")
      (node (ref "H2") (pin "1") (pinfunction "1_1") (pintype "passive"))
      (node (ref "S1") (pin "2") (pintype "passive"))
      (node (ref "U1") (pin "39") (pinfunction "~{NRST}_39") (pintype "bidirectional"))
    )
    (net (code "31") (name "3V3") (class "Default")
      (node (ref "C11") (pin "2") (pinfunction "2_2") (pintype "passive"))
      (node (ref "C13") (pin "2") (pinfunction "2_2") (pintype "passive"))
      (node (ref "C15") (pin "2") (pinfunction "2_2") (pintype "passive"))
      (node (ref "C17") (pin "2") (pinfunction "2_2") (pintype "passive"))
      (node (ref "C21") (pin "2") (pinfunction "2_2") (pintype "passive"))
      (node (ref "C9") (pin "2") (pinfunction "2_2") (pintype "passive"))
      (node (ref "H2") (pin "7") (pinfunction "7_7") (pintype "passive"))
      (node (ref "H2") (pin "8") (pinfunction "8_8") (pintype "passive"))
      (node (ref "P1") (pin "2") (pinfunction "2_2") (pintype "passive"))
      (node (ref "P2") (pin "2") (pinfunction "2_2") (pintype "passive"))
      (node (ref "P3") (pin "2") (pinfunction "2_2") (pintype "passive"))
      (node (ref "P4") (pin "2") (pinfunction "2_2") (pintype "passive"))
      (node (ref "R13") (pin "1") (pinfunction "1_1") (pintype "passive"))
      (node (ref "R23") (pin "1") (pinfunction "1_1") (pintype "passive"))
      (node (ref "R26") (pin "2") (pinfunction "2_2") (pintype "passive"))
      (node (ref "R27") (pin "2") (pinfunction "2_2") (pintype "passive"))
      (node (ref "R9") (pin "1") (pinfunction "1_1") (pintype "passive"))
      (node (ref "TP1") (pin "1") (pinfunction "1_1") (pintype "passive"))
      (node (ref "TP8") (pin "1") (pinfunction "1_1") (pintype "passive"))
      (node (ref "U1") (pin "1") (pinfunction "ADVREF_1") (pintype "input"))
      (node (ref "U1") (pin "18") (pinfunction "VDDIO_18") (pintype "power_in"))
      (node (ref "U1") (pin "45") (pinfunction "VDDIO_45") (pintype "power_in"))
      (node (ref "U1") (pin "58") (pinfunction "VDDIO_58") (pintype "power_in"))
      (node (ref "U1") (pin "7") (pinfunction "VDDIN_7") (pintype "power_in"))
      (node (ref "U4") (pin "5") (pinfunction "OUT_5") (pintype "power_in"))
      (node (ref "U6") (pin "7") (pinfunction "~{CS}_7") (pintype "input"))
      (node (ref "U7") (pin "6") (pinfunction "VCCB_6") (pintype "passive"))
    )
    (net (code "32") (name "3V3_B") (class "Default")
      (node (ref "C19") (pin "2") (pinfunction "2_2") (pintype "passive"))
      (node (ref "R8") (pin "2") (pinfunction "2_2") (pintype "passive"))
      (node (ref "TP23") (pin "1") (pinfunction "1_1") (pintype "passive"))
      (node (ref "U5") (pin "5") (pinfunction "OUT_5") (pintype "power_in"))
    )
    (net (code "33") (name "5V") (class "Default")
      (node (ref "C18") (pin "2") (pinfunction "2_2") (pintype "passive"))
      (node (ref "C20") (pin "2") (pinfunction "2_2") (pintype "passive"))
      (node (ref "J1") (pin "2") (pinfunction "C2_2") (pintype "passive"))
      (node (ref "R24") (pin "2") (pinfunction "2_2") (pintype "passive"))
      (node (ref "TP5") (pin "1") (pinfunction "1_1") (pintype "passive"))
      (node (ref "U4") (pin "1") (pinfunction "IN_1") (pintype "power_in"))
      (node (ref "U4") (pin "3") (pinfunction "EN_3") (pintype "input"))
      (node (ref "U5") (pin "1") (pinfunction "IN_1") (pintype "power_in"))
    )
    (net (code "34") (name "5V_REG") (class "Default")
      (node (ref "C5") (pin "2") (pinfunction "2_2") (pintype "passive"))
      (node (ref "C6") (pin "2") (pinfunction "2_2") (pintype "passive"))
      (node (ref "J1") (pin "1") (pinfunction "C1_1") (pintype "passive"))
      (node (ref "L2") (pin "2") (pintype "passive"))
      (node (ref "R21") (pin "1") (pinfunction "1_1") (pintype "passive"))
      (node (ref "TP19") (pin "1") (pinfunction "1_1") (pintype "passive"))
      (node (ref "U3") (pin "5") (pinfunction "FB_5") (pintype "input"))
      (node (ref "U7") (pin "1") (pinfunction "VCCA_1") (pintype "passive"))
    )
    (net (code "35") (name "GND") (class "Default")
      (node (ref "C1") (pin "1") (pinfunction "1_1") (pintype "passive"))
      (node (ref "C10") (pin "1") (pinfunction "1_1") (pintype "passive"))
      (node (ref "C11") (pin "1") (pinfunction "1_1") (pintype "passive"))
      (node (ref "C12") (pin "1") (pinfunction "1_1") (pintype "passive"))
      (node (ref "C13") (pin "1") (pinfunction "1_1") (pintype "passive"))
      (node (ref "C14") (pin "1") (pinfunction "1_1") (pintype "passive"))
      (node (ref "C15") (pin "1") (pinfunction "1_1") (pintype "passive"))
      (node (ref "C16") (pin "1") (pinfunction "1_1") (pintype "passive"))
      (node (ref "C17") (pin "1") (pinfunction "1_1") (pintype "passive"))
      (node (ref "C18") (pin "1") (pinfunction "1_1") (pintype "passive"))
      (node (ref "C19") (pin "1") (pinfunction "1_1") (pintype "passive"))
      (node (ref "C2") (pin "1") (pinfunction "1_1") (pintype "passive"))
      (node (ref "C20") (pin "1") (pinfunction "1_1") (pintype "passive"))
      (node (ref "C21") (pin "1") (pinfunction "1_1") (pintype "passive"))
      (node (ref "C23") (pin "1") (pinfunction "1_1") (pintype "passive"))
      (node (ref "C24") (pin "1") (pinfunction "1_1") (pintype "passive"))
      (node (ref "C25") (pin "1") (pinfunction "1_1") (pintype "passive"))
      (node (ref "C26") (pin "1") (pinfunction "1_1") (pintype "passive"))
      (node (ref "C4") (pin "1") (pinfunction "1_1") (pintype "passive"))
      (node (ref "C5") (pin "1") (pinfunction "1_1") (pintype "passive"))
      (node (ref "C6") (pin "1") (pinfunction "1_1") (pintype "passive"))
      (node (ref "C7") (pin "1") (pinfunction "1_1") (pintype "passive"))
      (node (ref "C8") (pin "1") (pinfunction "1_1") (pintype "passive"))
      (node (ref "C9") (pin "1") (pinfunction "1_1") (pintype "passive"))
      (node (ref "D1") (pin "1") (pinfunction "A_1") (pintype "passive"))
      (node (ref "H1") (pin "1") (pinfunction "GND_1") (pintype "passive"))
      (node (ref "H1") (pin "3") (pinfunction "GND_3") (pintype "passive"))
      (node (ref "H2") (pin "5") (pinfunction "5_5") (pintype "passive"))
      (node (ref "H2") (pin "6") (pinfunction "6_6") (pintype "passive"))
      (node (ref "H3") (pin "5") (pinfunction "GND_5") (pintype "passive"))
      (node (ref "H3") (pin "6") (pinfunction "SHLD_6") (pintype "passive"))
      (node (ref "P5") (pin "3") (pinfunction "3_3") (pintype "passive"))
      (node (ref "R14") (pin "1") (pinfunction "1_1") (pintype "passive"))
      (node (ref "R20") (pin "1") (pinfunction "1_1") (pintype "passive"))
      (node (ref "R4") (pin "1") (pinfunction "1_1") (pintype "passive"))
      (node (ref "R6") (pin "1") (pinfunction "1_1") (pintype "passive"))
      (node (ref "R7") (pin "1") (pinfunction "1_1") (pintype "passive"))
      (node (ref "S1") (pin "1") (pintype "passive"))
      (node (ref "S2") (pin "1") (pintype "passive"))
      (node (ref "S3") (pin "1") (pintype "passive"))
      (node (ref "S4") (pin "1") (pintype "passive"))
      (node (ref "T1") (pin "2") (pinfunction "2_2") (pintype "passive"))
      (node (ref "TP11") (pin "1") (pinfunction "1_1") (pintype "passive"))
      (node (ref "TP13") (pin "1") (pinfunction "1_1") (pintype "passive"))
      (node (ref "TP16") (pin "1") (pinfunction "1_1") (pintype "passive"))
      (node (ref "TP18") (pin "1") (pinfunction "1_1") (pintype "passive"))
      (node (ref "U1") (pin "17") (pinfunction "GND_17") (pintype "power_in"))
      (node (ref "U1") (pin "2") (pinfunction "GND_2") (pintype "power_in"))
      (node (ref "U1") (pin "46") (pinfunction "GND_46") (pintype "power_in"))
      (node (ref "U1") (pin "60") (pinfunction "GND_60") (pintype "power_in"))
      (node (ref "U2") (pin "2") (pinfunction "GND_2") (pintype "passive"))
      (node (ref "U3") (pin "7") (pinfunction "GND_7") (pintype "power_in"))
      (node (ref "U3") (pin "EPAD") (pinfunction "EPAD_EPAD") (pintype "passive"))
      (node (ref "U4") (pin "2") (pinfunction "GND_2") (pintype "power_in"))
      (node (ref "U5") (pin "2") (pinfunction "GND_2") (pintype "power_in"))
      (node (ref "U6") (pin "12") (pinfunction "SDO/ALT_ADDRESS_12") (pintype "bidirectional"))
      (node (ref "U6") (pin "2") (pinfunction "GND_2") (pintype "power_in"))
      (node (ref "U6") (pin "4") (pinfunction "GND_4") (pintype "power_in"))
      (node (ref "U6") (pin "5") (pinfunction "GND_5") (pintype "power_in"))
      (node (ref "U7") (pin "2") (pinfunction "GND_2") (pintype "passive"))
      (node (ref "U7") (pin "5") (pinfunction "DIR_5") (pintype "passive"))
    )
    (net (code "36") (name "Net-(C22-Pad2)") (class "Default")
      (node (ref "C22") (pin "2") (pinfunction "2_2") (pintype "passive"))
      (node (ref "R20") (pin "2") (pinfunction "2_2") (pintype "passive"))
    )
    (net (code "37") (name "Net-(C24-Pad2)") (class "Default")
      (node (ref "C24") (pin "2") (pinfunction "2_2") (pintype "passive"))
      (node (ref "P5") (pin "1") (pinfunction "1_1") (pintype "passive"))
      (node (ref "R21") (pin "2") (pinfunction "2_2") (pintype "passive"))
    )
    (net (code "38") (name "Net-(D1-K)") (class "Default")
      (node (ref "C3") (pin "2") (pinfunction "2_2") (pintype "passive"))
      (node (ref "D1") (pin "2") (pinfunction "K_2") (pintype "passive"))
      (node (ref "L2") (pin "1") (pintype "passive"))
      (node (ref "U3") (pin "8") (pinfunction "SW_8") (pintype "output"))
    )
    (net (code "39") (name "Net-(DL1-A)") (class "Default")
      (node (ref "DL1") (pin "2") (pinfunction "A_2") (pintype "passive"))
      (node (ref "R9") (pin "2") (pinfunction "2_2") (pintype "passive"))
    )
    (net (code "40") (name "Net-(DL2-A)") (class "Default")
      (node (ref "DL2") (pin "2") (pinfunction "A_2") (pintype "passive"))
      (node (ref "R13") (pin "2") (pinfunction "2_2") (pintype "passive"))
    )
    (net (code "41") (name "Net-(F1-Pad2)") (class "Default")
      (node (ref "F1") (pin "2") (pinfunction "2_2") (pintype "passive"))
      (node (ref "Q1") (pin "3") (pinfunction "3_3") (pintype "passive"))
    )
    (net (code "42") (name "Net-(H1-VBATT)") (class "Default")
      (node (ref "F1") (pin "1") (pinfunction "1_1") (pintype "passive"))
      (node (ref "H1") (pin "2") (pinfunction "VBATT_2") (pintype "passive"))
    )
    (net (code "43") (name "Net-(L1-Pad2)") (class "Default")
      (node (ref "L1") (pin "2") (pinfunction "2_2") (pintype "passive"))
      (node (ref "R8") (pin "1") (pinfunction "1_1") (pintype "passive"))
    )
    (net (code "44") (name "Net-(P1-Pad1)") (class "Default")
      (node (ref "P1") (pin "1") (pinfunction "1_1") (pintype "passive"))
      (node (ref "R16") (pin "2") (pinfunction "2_2") (pintype "passive"))
    )
    (net (code "45") (name "Net-(P2-Pad1)") (class "Default")
      (node (ref "P2") (pin "1") (pinfunction "1_1") (pintype "passive"))
      (node (ref "R17") (pin "2") (pinfunction "2_2") (pintype "passive"))
    )
    (net (code "46") (name "Net-(P3-Pad1)") (class "Default")
      (node (ref "P3") (pin "1") (pinfunction "1_1") (pintype "passive"))
      (node (ref "R18") (pin "2") (pinfunction "2_2") (pintype "passive"))
    )
    (net (code "47") (name "Net-(P4-Pad1)") (class "Default")
      (node (ref "P4") (pin "1") (pinfunction "1_1") (pintype "passive"))
      (node (ref "R19") (pin "2") (pinfunction "2_2") (pintype "passive"))
    )
    (net (code "48") (name "Net-(P5-Pad2)") (class "Default")
      (node (ref "P5") (pin "2") (pinfunction "2_2") (pintype "passive"))
      (node (ref "R22") (pin "2") (pinfunction "2_2") (pintype "passive"))
    )
    (net (code "49") (name "Net-(P7-Pad1)") (class "Default")
      (node (ref "P7") (pin "1") (pinfunction "1_1") (pintype "passive"))
      (node (ref "R24") (pin "1") (pinfunction "1_1") (pintype "passive"))
      (node (ref "R25") (pin "2") (pinfunction "2_2") (pintype "passive"))
    )
    (net (code "50") (name "Net-(P7-Pad2)") (class "Default")
      (node (ref "P7") (pin "2") (pinfunction "2_2") (pintype "passive"))
      (node (ref "R25") (pin "1") (pinfunction "1_1") (pintype "passive"))
      (node (ref "T1") (pin "3") (pinfunction "3_3") (pintype "passive"))
    )
    (net (code "51") (name "Net-(Q1-Pad1)") (class "Default")
      (node (ref "Q1") (pin "1") (pinfunction "1_1") (pintype "passive"))
      (node (ref "R6") (pin "2") (pinfunction "2_2") (pintype "passive"))
    )
    (net (code "52") (name "Net-(R28-Pad2)") (class "Default")
      (node (ref "R28") (pin "2") (pinfunction "2_2") (pintype "passive"))
      (node (ref "T1") (pin "1") (pinfunction "1_1") (pintype "passive"))
    )
    (net (code "53") (name "Net-(U1A-PB8{slash}XOUT)") (class "Default")
      (node (ref "C2") (pin "2") (pinfunction "2_2") (pintype "passive"))
      (node (ref "U1") (pin "61") (pinfunction "PB8/XOUT_61") (pintype "bidirectional"))
      (node (ref "Y1") (pin "1") (pinfunction "OSC1_1") (pintype "passive"))
    )
    (net (code "54") (name "Net-(U1A-PB9{slash}XIN)") (class "Default")
      (node (ref "C1") (pin "2") (pinfunction "2_2") (pintype "passive"))
      (node (ref "U1") (pin "62") (pinfunction "PB9/XIN_62") (pintype "bidirectional"))
      (node (ref "Y1") (pin "3") (pinfunction "OSC2_3") (pintype "passive"))
    )
    (net (code "55") (name "Net-(U1A-PB10{slash}DDM)") (class "Default")
      (node (ref "R3") (pin "2") (pinfunction "2_2") (pintype "passive"))
      (node (ref "U1") (pin "56") (pinfunction "PB10/DDM_56") (pintype "bidirectional"))
    )
    (net (code "56") (name "Net-(U1A-PB11{slash}DDP)") (class "Default")
      (node (ref "R2") (pin "2") (pinfunction "2_2") (pintype "passive"))
      (node (ref "U1") (pin "57") (pinfunction "PB11/DDP_57") (pintype "bidirectional"))
    )
    (net (code "57") (name "Net-(U1A-PB12{slash}ERASE)") (class "Default")
      (node (ref "TP2") (pin "1") (pinfunction "1_1") (pintype "passive"))
      (node (ref "U1") (pin "55") (pinfunction "PB12/ERASE_55") (pintype "bidirectional"))
    )
    (net (code "58") (name "Net-(U1B-VDDOUT)") (class "Default")
      (node (ref "C10") (pin "2") (pinfunction "2_2") (pintype "passive"))
      (node (ref "C12") (pin "2") (pinfunction "2_2") (pintype "passive"))
      (node (ref "C14") (pin "2") (pinfunction "2_2") (pintype "passive"))
      (node (ref "C16") (pin "2") (pinfunction "2_2") (pintype "passive"))
      (node (ref "L3") (pin "2") (pinfunction "2_2") (pintype "passive"))
      (node (ref "U1") (pin "12") (pinfunction "VDDCORE_12") (pintype "power_in"))
      (node (ref "U1") (pin "24") (pinfunction "VDDCORE_24") (pintype "power_in"))
      (node (ref "U1") (pin "54") (pinfunction "VDDCORE_54") (pintype "power_in"))
      (node (ref "U1") (pin "8") (pinfunction "VDDOUT_8") (pintype "power_in"))
    )
    (net (code "59") (name "Net-(U1B-VDDPLL)") (class "Default")
      (node (ref "C22") (pin "1") (pinfunction "1_1") (pintype "passive"))
      (node (ref "C23") (pin "2") (pinfunction "2_2") (pintype "passive"))
      (node (ref "L3") (pin "1") (pinfunction "1_1") (pintype "passive"))
      (node (ref "U1") (pin "64") (pinfunction "VDDPLL_64") (pintype "power_in"))
    )
    (net (code "60") (name "Net-(U2-VCC)") (class "Default")
      (node (ref "C4") (pin "2") (pinfunction "2_2") (pintype "passive"))
      (node (ref "L1") (pin "1") (pinfunction "1_1") (pintype "passive"))
      (node (ref "U2") (pin "1") (pinfunction "VCC_1") (pintype "passive"))
    )
    (net (code "61") (name "Net-(U3-BST)") (class "Default")
      (node (ref "C3") (pin "1") (pinfunction "1_1") (pintype "passive"))
      (node (ref "U3") (pin "1") (pinfunction "BST_1") (pintype "passive"))
    )
    (net (code "62") (name "Net-(U3-EN)") (class "Default")
      (node (ref "R11") (pin "1") (pinfunction "1_1") (pintype "passive"))
      (node (ref "R14") (pin "2") (pinfunction "2_2") (pintype "passive"))
      (node (ref "U3") (pin "3") (pinfunction "EN_3") (pintype "input"))
    )
    (net (code "63") (name "Net-(U3-PGOOD)") (class "Default")
      (node (ref "R12") (pin "1") (pinfunction "1_1") (pintype "passive"))
      (node (ref "U3") (pin "4") (pinfunction "PGOOD_4") (pintype "output"))
    )
    (net (code "64") (name "Net-(U6-VDD_I{slash}O)") (class "Default")
      (node (ref "C25") (pin "2") (pinfunction "2_2") (pintype "passive"))
      (node (ref "C26") (pin "2") (pinfunction "2_2") (pintype "passive"))
      (node (ref "R23") (pin "2") (pinfunction "2_2") (pintype "passive"))
      (node (ref "U6") (pin "1") (pinfunction "VDD_I/O_1") (pintype "power_in"))
      (node (ref "U6") (pin "6") (pinfunction "VS_6") (pintype "power_in"))
    )
    (net (code "65") (name "RADIO_CE") (class "Default")
      (node (ref "TP22") (pin "1") (pinfunction "1_1") (pintype "passive"))
      (node (ref "U1") (pin "29") (pinfunction "PA10_29") (pintype "bidirectional"))
      (node (ref "U2") (pin "3") (pinfunction "CE_3") (pintype "passive"))
    )
    (net (code "66") (name "RADIO_CLK") (class "Default")
      (node (ref "TP24") (pin "1") (pinfunction "1_1") (pintype "passive"))
      (node (ref "U1") (pin "21") (pinfunction "SPCK/PWMH3/PA14_21") (pintype "bidirectional"))
      (node (ref "U2") (pin "5") (pinfunction "SCK_5") (pintype "passive"))
    )
    (net (code "67") (name "RADIO_CSN") (class "Default")
      (node (ref "TP21") (pin "1") (pinfunction "1_1") (pintype "passive"))
      (node (ref "U1") (pin "28") (pinfunction "PWMH0/PA11_28") (pintype "bidirectional"))
      (node (ref "U2") (pin "4") (pinfunction "CSN_4") (pintype "passive"))
    )
    (net (code "68") (name "RADIO_IRQ") (class "Default")
      (node (ref "TP20") (pin "1") (pinfunction "1_1") (pintype "passive"))
      (node (ref "U1") (pin "23") (pinfunction "PWMH1/PA24_23") (pintype "bidirectional"))
      (node (ref "U2") (pin "8") (pinfunction "IRQ_8") (pintype "passive"))
    )
    (net (code "69") (name "SWCLK") (class "Default")
      (node (ref "H2") (pin "2") (pinfunction "2_2") (pintype "passive"))
      (node (ref "TP26") (pin "1") (pinfunction "1_1") (pintype "passive"))
      (node (ref "U1") (pin "53") (pinfunction "PB7/SWCLK/TCK_53") (pintype "bidirectional"))
    )
    (net (code "70") (name "SWDIO") (class "Default")
      (node (ref "H2") (pin "4") (pinfunction "4_4") (pintype "passive"))
      (node (ref "TP25") (pin "1") (pinfunction "1_1") (pintype "passive"))
      (node (ref "U1") (pin "51") (pinfunction "PB6/SWDIO/TMS_51") (pintype "bidirectional"))
    )
    (net (code "71") (name "VBUS") (class "Default")
      (node (ref "H3") (pin "1") (pinfunction "VBUS_1") (pintype "power_in"))
      (node (ref "J1") (pin "3") (pinfunction "C3_3") (pintype "passive"))
      (node (ref "R1") (pin "2") (pinfunction "2_2") (pintype "passive"))
    )
    (net (code "72") (name "unconnected-(H2-Pad3)") (class "Default")
      (node (ref "H2") (pin "3") (pinfunction "3_3") (pintype "passive+no_connect"))
    )
    (net (code "73") (name "unconnected-(H2-Pad9)") (class "Default")
      (node (ref "H2") (pin "9") (pinfunction "9_9") (pintype "passive+no_connect"))
    )
    (net (code "74") (name "unconnected-(H2-Pad10)") (class "Default")
      (node (ref "H2") (pin "10") (pinfunction "10_10") (pintype "passive+no_connect"))
    )
    (net (code "75") (name "unconnected-(H3-ID-Pad4)") (class "Default")
      (node (ref "H3") (pin "4") (pinfunction "ID_4") (pintype "power_in+no_connect"))
    )
    (net (code "76") (name "unconnected-(U1A-AD0{slash}PWMH3{slash}PA17-Pad9)") (class "Default")
      (node (ref "U1") (pin "9") (pinfunction "AD0/PWMH3/PA17_9") (pintype "bidirectional+no_connect"))
    )
    (net (code "77") (name "unconnected-(U1A-AD1{slash}PA18-Pad10)") (class "Default")
      (node (ref "U1") (pin "10") (pinfunction "AD1/PA18_10") (pintype "bidirectional+no_connect"))
    )
    (net (code "78") (name "unconnected-(U1A-JTAGSEL-Pad50)") (class "Default")
      (node (ref "U1") (pin "50") (pinfunction "JTAGSEL_50") (pintype "input+no_connect"))
    )
    (net (code "79") (name "unconnected-(U1A-PA9-Pad30)") (class "Default")
      (node (ref "U1") (pin "30") (pinfunction "PA9_30") (pintype "bidirectional+no_connect"))
    )
    (net (code "80") (name "unconnected-(U1A-PB1{slash}PWMH1{slash}AD5-Pad4)") (class "Default")
      (node (ref "U1") (pin "4") (pinfunction "PB1/PWMH1/AD5_4") (pintype "bidirectional+no_connect"))
    )
    (net (code "81") (name "unconnected-(U1A-PB2{slash}AD6-Pad5)") (class "Default")
      (node (ref "U1") (pin "5") (pinfunction "PB2/AD6_5") (pintype "bidirectional+no_connect"))
    )
    (net (code "82") (name "unconnected-(U1A-PB3{slash}AD7-Pad6)") (class "Default")
      (node (ref "U1") (pin "6") (pinfunction "PB3/AD7_6") (pintype "bidirectional+no_connect"))
    )
    (net (code "83") (name "unconnected-(U1A-PB13{slash}PWML2{slash}DAC0-Pad59)") (class "Default")
      (node (ref "U1") (pin "59") (pinfunction "PB13/PWML2/DAC0_59") (pintype "bidirectional+no_connect"))
    )
    (net (code "84") (name "unconnected-(U1A-PB14{slash}PWMH3{slash}DAC1-Pad63)") (class "Default")
      (node (ref "U1") (pin "63") (pinfunction "PB14/PWMH3/DAC1_63") (pintype "bidirectional+no_connect"))
    )
    (net (code "85") (name "unconnected-(U1A-PWMH0{slash}PA23-Pad15)") (class "Default")
      (node (ref "U1") (pin "15") (pinfunction "PWMH0/PA23_15") (pintype "bidirectional+no_connect"))
    )
    (net (code "86") (name "unconnected-(U1A-PWML2{slash}PA16-Pad19)") (class "Default")
      (node (ref "U1") (pin "19") (pinfunction "PWML2/PA16_19") (pintype "bidirectional+no_connect"))
    )
    (net (code "87") (name "unconnected-(U1A-PWML3{slash}PA15-Pad20)") (class "Default")
      (node (ref "U1") (pin "20") (pinfunction "PWML3/PA15_20") (pintype "bidirectional+no_connect"))
    )
    (net (code "88") (name "unconnected-(U1A-RXD0{slash}PA5-Pad35)") (class "Default")
      (node (ref "U1") (pin "35") (pinfunction "RXD0/PA5_35") (pintype "bidirectional+no_connect"))
    )
    (net (code "89") (name "unconnected-(U1A-TST-Pad40)") (class "Default")
      (node (ref "U1") (pin "40") (pinfunction "TST_40") (pintype "input+no_connect"))
    )
    (net (code "90") (name "unconnected-(U3-NC-Pad6)") (class "Default")
      (node (ref "U3") (pin "6") (pinfunction "NC_6") (pintype "passive+no_connect"))
    )
    (net (code "91") (name "unconnected-(U4-BYP-Pad4)") (class "Default")
      (node (ref "U4") (pin "4") (pinfunction "BYP_4") (pintype "passive+no_connect"))
    )
    (net (code "92") (name "unconnected-(U5-BYP-Pad4)") (class "Default")
      (node (ref "U5") (pin "4") (pinfunction "BYP_4") (pintype "passive+no_connect"))
    )
    (net (code "93") (name "unconnected-(U6-NC-Pad10)") (class "Default")
      (node (ref "U6") (pin "10") (pinfunction "NC_10") (pintype "passive+no_connect"))
    )
    (net (code "94") (name "unconnected-(U6-RESERVED-Pad3)") (class "Default")
      (node (ref "U6") (pin "3") (pinfunction "RESERVED_3") (pintype "passive+no_connect"))
    )
    (net (code "95") (name "unconnected-(U6-RESERVED-Pad11)") (class "Default")
      (node (ref "U6") (pin "11") (pinfunction "RESERVED_11") (pintype "passive+no_connect"))
    )
  )
)
